# schemat_Czujnik_w.net
KiCad netlist of a schematic drawn in EAGLE
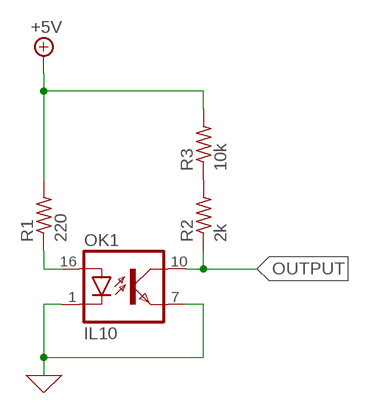
[diagram p0: schematic, sheet 1]

(export (version "E")
  (design (tool "Eeschema 10.0.6"))
  (components
    (comp (ref "OK1")
      (value "IL10")
      (footprint "eagle-import:DIL16-4_1_7_10_16")
      (libsource (lib "eagle-import") (part "IL10"))
    )
    (comp (ref "R1")
      (value "220")
      (footprint "eagle-import:0207_10")
      (libsource (lib "eagle-import") (part "R-US_0207/10"))
    )
    (comp (ref "R2")
      (value "2k")
      (footprint "eagle-import:0207_10")
      (libsource (lib "eagle-import") (part "R-US_0207/10"))
    )
    (comp (ref "R3")
      (value "10k")
      (footprint "eagle-import:0207_10")
      (libsource (lib "eagle-import") (part "R-US_0207/10"))
    )
  )
  (nets
    (net (code "1") (name "+5V") (class "Default")
      (node (ref "R1") (pin "2") (pinfunction "2_2") (pintype "passive"))
      (node (ref "R3") (pin "2") (pinfunction "2_2") (pintype "passive"))
    )
    (net (code "2") (name "GND") (class "Default")
      (node (ref "OK1") (pin "1") (pinfunction "C_1") (pintype "passive"))
      (node (ref "OK1") (pin "7") (pinfunction "EMIT_7") (pintype "passive"))
    )
    (net (code "3") (name "Net-(OK1-A)") (class "Default")
      (node (ref "OK1") (pin "16") (pinfunction "A_16") (pintype "passive"))
      (node (ref "R1") (pin "1") (pinfunction "1_1") (pintype "passive"))
    )
    (net (code "4") (name "Net-(R2-Pad2)") (class "Default")
      (node (ref "R2") (pin "2") (pinfunction "2_2") (pintype "passive"))
      (node (ref "R3") (pin "1") (pinfunction "1_1") (pintype "passive"))
    )
    (net (code "5") (name "OUTPUT") (class "Default")
      (node (ref "OK1") (pin "10") (pinfunction "COL_10") (pintype "passive"))
      (node (ref "R2") (pin "1") (pinfunction "1_1") (pintype "passive"))
    )
  )
)
